# Grove_-_NFC_v1_1.net
KiCad netlist of a schematic drawn in EAGLE
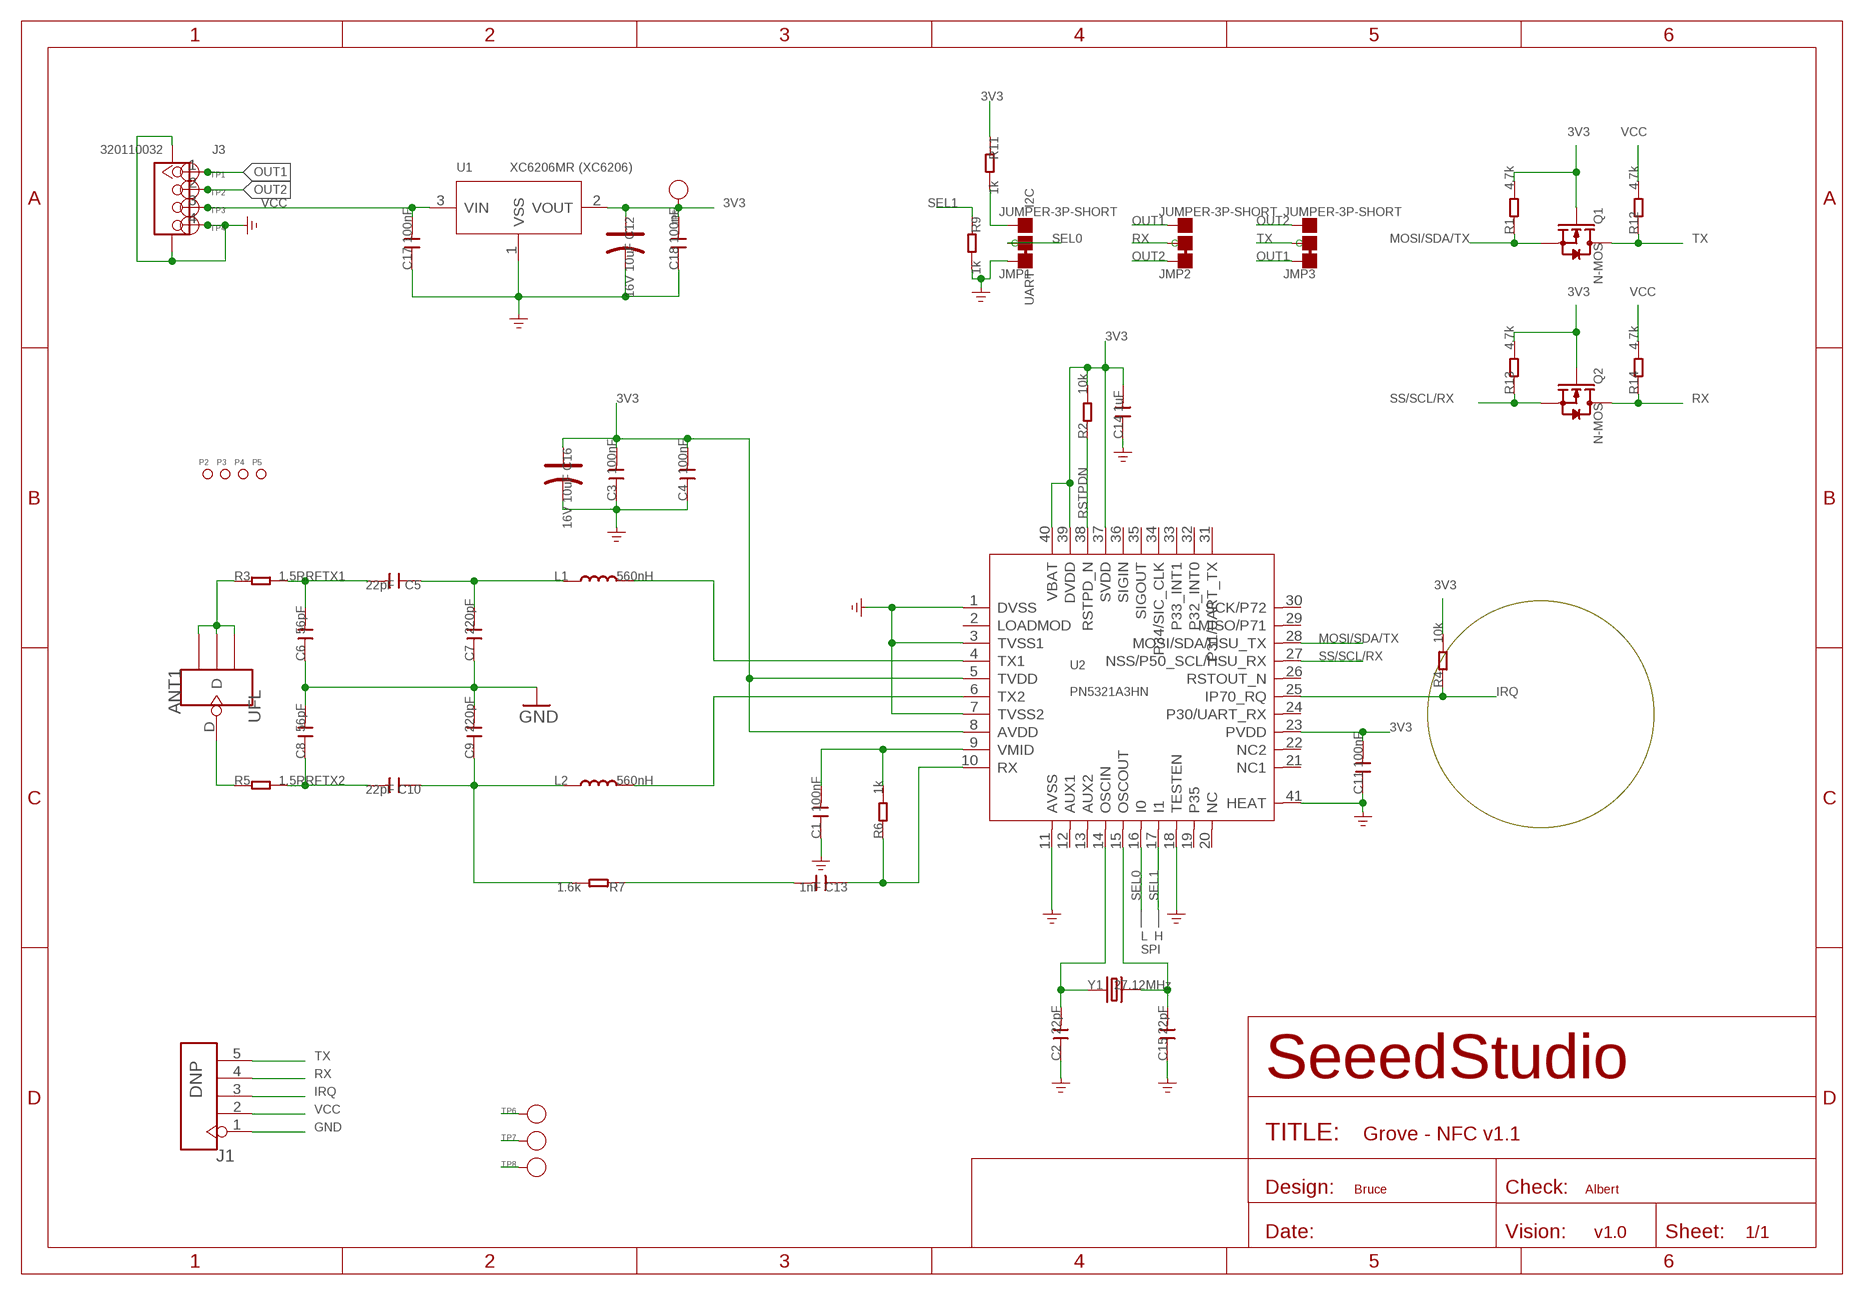
[diagram p0: schematic, sheet 1]

(export (version "E")
  (design (tool "Eeschema 10.0.6"))
  (components
    (comp (ref "ANT1")
      (value "UFL")
      (footprint "eagle-import:4P-U-FL")
      (libsource (lib "eagle-import") (part "ANTENNA-U-FL"))
    )
    (comp (ref "C1")
      (value "100nF")
      (footprint "eagle-import:C0402")
      (libsource (lib "eagle-import") (part "C-0402"))
    )
    (comp (ref "C2")
      (value "22pF")
      (footprint "eagle-import:C0402")
      (libsource (lib "eagle-import") (part "C-0402"))
    )
    (comp (ref "C3")
      (value "100nF")
      (footprint "eagle-import:C0402")
      (libsource (lib "eagle-import") (part "C-0402"))
    )
    (comp (ref "C4")
      (value "100nF")
      (footprint "eagle-import:C0402")
      (libsource (lib "eagle-import") (part "C-0402"))
    )
    (comp (ref "C5")
      (value "22pF")
      (footprint "eagle-import:C0402")
      (libsource (lib "eagle-import") (part "C-0402"))
    )
    (comp (ref "C6")
      (value "56pF")
      (footprint "eagle-import:C0402")
      (libsource (lib "eagle-import") (part "C-0402"))
    )
    (comp (ref "C7")
      (value "220pF")
      (footprint "eagle-import:C0402")
      (libsource (lib "eagle-import") (part "C-0402"))
    )
    (comp (ref "C8")
      (value "56pF")
      (footprint "eagle-import:C0402")
      (libsource (lib "eagle-import") (part "C-0402"))
    )
    (comp (ref "C9")
      (value "220pF")
      (footprint "eagle-import:C0402")
      (libsource (lib "eagle-import") (part "C-0402"))
    )
    (comp (ref "C10")
      (value "22pF")
      (footprint "eagle-import:C0402")
      (libsource (lib "eagle-import") (part "C-0402"))
    )
    (comp (ref "C11")
      (value "100nF")
      (footprint "eagle-import:C0402")
      (libsource (lib "eagle-import") (part "C-0402"))
    )
    (comp (ref "C12")
      (value "16V 10uF")
      (footprint "eagle-import:AVX-A")
      (libsource (lib "eagle-import") (part "CAP-AVX-A"))
    )
    (comp (ref "C13")
      (value "1nF")
      (footprint "eagle-import:C0402")
      (libsource (lib "eagle-import") (part "C-0402"))
    )
    (comp (ref "C14")
      (value "1uF")
      (footprint "eagle-import:C0603")
      (libsource (lib "eagle-import") (part "C-0603"))
    )
    (comp (ref "C15")
      (value "22pF")
      (footprint "eagle-import:C0402")
      (libsource (lib "eagle-import") (part "C-0402"))
    )
    (comp (ref "C16")
      (value "16V 10uF")
      (footprint "eagle-import:AVX-A")
      (libsource (lib "eagle-import") (part "CAP-AVX-A"))
    )
    (comp (ref "C17")
      (value "100nF")
      (footprint "eagle-import:C0402")
      (libsource (lib "eagle-import") (part "C-0402"))
    )
    (comp (ref "C18")
      (value "100nF")
      (footprint "eagle-import:C0402")
      (libsource (lib "eagle-import") (part "C-0402"))
    )
    (comp (ref "J1")
      (value "DNP")
      (footprint "eagle-import:5P-2.54")
      (libsource (lib "eagle-import") (part "HEADER-5P-2.54"))
    )
    (comp (ref "J3")
      (value "320110032")
      (footprint "eagle-import:4P-SMD-2.0-90D")
      (libsource (lib "eagle-import") (part "GROVE-CONNECTOR-SMD'90D'"))
    )
    (comp (ref "JMP1")
      (value "JUMPER-3P-SHORT")
      (footprint "eagle-import:3P-SMD_SHORT")
      (libsource (lib "eagle-import") (part "JUMPER-3P-SHORT"))
    )
    (comp (ref "JMP2")
      (value "JUMPER-3P-SHORT")
      (footprint "eagle-import:3P-SMD_SHORT")
      (libsource (lib "eagle-import") (part "JUMPER-3P-SHORT"))
    )
    (comp (ref "JMP3")
      (value "JUMPER-3P-SHORT")
      (footprint "eagle-import:3P-SMD_SHORT")
      (libsource (lib "eagle-import") (part "JUMPER-3P-SHORT"))
    )
    (comp (ref "L1")
      (value "560nH")
      (footprint "eagle-import:L0603")
      (libsource (lib "eagle-import") (part "L'0603'"))
    )
    (comp (ref "L2")
      (value "560nH")
      (footprint "eagle-import:L0603")
      (libsource (lib "eagle-import") (part "L'0603'"))
    )
    (comp (ref "P2")
      (value "DNP")
      (footprint "eagle-import:ROUND-MARK-1.0")
      (libsource (lib "eagle-import") (part "PAD-MARK"))
    )
    (comp (ref "P3")
      (value "DNP")
      (footprint "eagle-import:ROUND-MARK-1.0")
      (libsource (lib "eagle-import") (part "PAD-MARK"))
    )
    (comp (ref "P4")
      (value "DNP")
      (footprint "eagle-import:ROUND-MARK-1.0")
      (libsource (lib "eagle-import") (part "PAD-MARK"))
    )
    (comp (ref "P5")
      (value "DNP")
      (footprint "eagle-import:ROUND-MARK-1.0")
      (libsource (lib "eagle-import") (part "PAD-MARK"))
    )
    (comp (ref "Q1")
      (value "N-MOS")
      (footprint "eagle-import:SOT23")
      (libsource (lib "eagle-import") (part "MOSFET-N'SOT23'"))
    )
    (comp (ref "Q2")
      (value "N-MOS")
      (footprint "eagle-import:SOT23")
      (libsource (lib "eagle-import") (part "MOSFET-N'SOT23'"))
    )
    (comp (ref "R1")
      (value "4.7k")
      (footprint "eagle-import:R0402")
      (libsource (lib "eagle-import") (part "R-0402"))
    )
    (comp (ref "R2")
      (value "10k")
      (footprint "eagle-import:R0402")
      (libsource (lib "eagle-import") (part "R-0402"))
    )
    (comp (ref "R3")
      (value "1.5R")
      (footprint "eagle-import:R0402")
      (libsource (lib "eagle-import") (part "R-0402"))
    )
    (comp (ref "R4")
      (value "10k")
      (footprint "eagle-import:R0402")
      (libsource (lib "eagle-import") (part "R-0402"))
    )
    (comp (ref "R5")
      (value "1.5R")
      (footprint "eagle-import:R0402")
      (libsource (lib "eagle-import") (part "R-0402"))
    )
    (comp (ref "R6")
      (value "1k")
      (footprint "eagle-import:R0402")
      (libsource (lib "eagle-import") (part "R-0402"))
    )
    (comp (ref "R7")
      (value "1.6k")
      (footprint "eagle-import:R0402")
      (libsource (lib "eagle-import") (part "R-0402"))
    )
    (comp (ref "R9")
      (value "1k")
      (footprint "eagle-import:R0402")
      (libsource (lib "eagle-import") (part "R-0402"))
    )
    (comp (ref "R11")
      (value "1k")
      (footprint "eagle-import:R0402")
      (libsource (lib "eagle-import") (part "R-0402"))
    )
    (comp (ref "R12")
      (value "4.7k")
      (footprint "eagle-import:R0402")
      (libsource (lib "eagle-import") (part "R-0402"))
    )
    (comp (ref "R13")
      (value "4.7k")
      (footprint "eagle-import:R0402")
      (libsource (lib "eagle-import") (part "R-0402"))
    )
    (comp (ref "R14")
      (value "4.7k")
      (footprint "eagle-import:R0402")
      (libsource (lib "eagle-import") (part "R-0402"))
    )
    (comp (ref "TP1")
      (value "DNP")
      (footprint "eagle-import:TP_4545")
      (libsource (lib "eagle-import") (part "PAD-TEST-POINT'4545'"))
    )
    (comp (ref "TP2")
      (value "DNP")
      (footprint "eagle-import:TP_4545")
      (libsource (lib "eagle-import") (part "PAD-TEST-POINT'4545'"))
    )
    (comp (ref "TP3")
      (value "DNP")
      (footprint "eagle-import:TP_4545")
      (libsource (lib "eagle-import") (part "PAD-TEST-POINT'4545'"))
    )
    (comp (ref "TP4")
      (value "DNP")
      (footprint "eagle-import:TP_4545")
      (libsource (lib "eagle-import") (part "PAD-TEST-POINT'4545'"))
    )
    (comp (ref "TP5")
      (value "DNP")
      (footprint "eagle-import:TP_4545")
      (libsource (lib "eagle-import") (part "PAD-TEST-POINT'4545'"))
    )
    (comp (ref "TP6")
      (value "DNP")
      (footprint "eagle-import:TP_4545")
      (libsource (lib "eagle-import") (part "PAD-TEST-POINT'4545'"))
    )
    (comp (ref "TP7")
      (value "DNP")
      (footprint "eagle-import:TP_4545")
      (libsource (lib "eagle-import") (part "PAD-TEST-POINT'4545'"))
    )
    (comp (ref "TP8")
      (value "DNP")
      (footprint "eagle-import:TP_4545")
      (libsource (lib "eagle-import") (part "PAD-TEST-POINT'4545'"))
    )
    (comp (ref "U1")
      (value "XC6206MR (XC6206)")
      (footprint "eagle-import:SOT-23")
      (libsource (lib "eagle-import") (part "PMIC-XC6206PMR"))
    )
    (comp (ref "U2")
      (value "PN5321A3HN")
      (footprint "eagle-import:HVQFN40")
      (libsource (lib "eagle-import") (part "PN532-HVQFN40"))
    )
    (comp (ref "Y1")
      (value "27.12MHz")
      (footprint "eagle-import:4P-SMD-3.2X2.5")
      (libsource (lib "eagle-import") (part "CRYSTAL'3225'"))
    )
  )
  (nets
    (net (code "1") (name "/3V3") (class "Default")
      (node (ref "C11") (pin "2") (pinfunction "2_2") (pintype "passive"))
      (node (ref "C12") (pin "+") (pinfunction "+_+") (pintype "passive"))
      (node (ref "C14") (pin "2") (pinfunction "2_2") (pintype "passive"))
      (node (ref "C16") (pin "+") (pinfunction "+_+") (pintype "passive"))
      (node (ref "C18") (pin "2") (pinfunction "2_2") (pintype "passive"))
      (node (ref "C3") (pin "2") (pinfunction "2_2") (pintype "passive"))
      (node (ref "C4") (pin "2") (pinfunction "2_2") (pintype "passive"))
      (node (ref "Q1") (pin "1") (pinfunction "G_1") (pintype "passive"))
      (node (ref "Q2") (pin "1") (pinfunction "G_1") (pintype "passive"))
      (node (ref "R1") (pin "2") (pinfunction "2_2") (pintype "passive"))
      (node (ref "R11") (pin "1") (pinfunction "1_1") (pintype "passive"))
      (node (ref "R13") (pin "2") (pinfunction "2_2") (pintype "passive"))
      (node (ref "R2") (pin "2") (pinfunction "2_2") (pintype "passive"))
      (node (ref "R4") (pin "2") (pinfunction "2_2") (pintype "passive"))
      (node (ref "TP5") (pin "T") (pinfunction "T_T") (pintype "bidirectional"))
      (node (ref "U1") (pin "2") (pinfunction "VOUT_2") (pintype "output"))
      (node (ref "U2") (pin "23") (pinfunction "PVDD_23") (pintype "power_in"))
      (node (ref "U2") (pin "37") (pinfunction "SVDD_37") (pintype "power_in"))
      (node (ref "U2") (pin "39") (pinfunction "DVDD_39") (pintype "power_in"))
      (node (ref "U2") (pin "40") (pinfunction "VBAT_40") (pintype "power_in"))
      (node (ref "U2") (pin "5") (pinfunction "TVDD_5") (pintype "power_in"))
      (node (ref "U2") (pin "8") (pinfunction "AVDD_8") (pintype "power_in"))
    )
    (net (code "2") (name "/IRQ") (class "Default")
      (node (ref "J1") (pin "3") (pinfunction "3_3") (pintype "bidirectional"))
      (node (ref "R4") (pin "1") (pinfunction "1_1") (pintype "passive"))
      (node (ref "U2") (pin "25") (pinfunction "IP70_RQ_25") (pintype "output"))
    )
    (net (code "3") (name "/MOSI{slash}SDA{slash}TX") (class "Default")
      (node (ref "Q1") (pin "2") (pinfunction "S_2") (pintype "passive"))
      (node (ref "R1") (pin "1") (pinfunction "1_1") (pintype "passive"))
      (node (ref "U2") (pin "28") (pinfunction "MOSI/SDA/HSU_TX_28") (pintype "bidirectional"))
    )
    (net (code "4") (name "/RFTX1") (class "Default")
      (node (ref "C5") (pin "2") (pinfunction "2_2") (pintype "passive"))
      (node (ref "C6") (pin "2") (pinfunction "2_2") (pintype "passive"))
      (node (ref "R3") (pin "2") (pinfunction "2_2") (pintype "passive"))
    )
    (net (code "5") (name "/RFTX2") (class "Default")
      (node (ref "C10") (pin "2") (pinfunction "2_2") (pintype "passive"))
      (node (ref "C8") (pin "1") (pinfunction "1_1") (pintype "passive"))
      (node (ref "R5") (pin "2") (pinfunction "2_2") (pintype "passive"))
    )
    (net (code "6") (name "/RSTPDN") (class "Default")
      (node (ref "R2") (pin "1") (pinfunction "1_1") (pintype "passive"))
      (node (ref "U2") (pin "38") (pinfunction "RSTPD_N_38") (pintype "input"))
    )
    (net (code "7") (name "/RX") (class "Default")
      (node (ref "J1") (pin "4") (pinfunction "4_4") (pintype "bidirectional"))
      (node (ref "JMP2") (pin "MM") (pinfunction "C_MM") (pintype "bidirectional"))
      (node (ref "Q2") (pin "3") (pinfunction "D_3") (pintype "passive"))
      (node (ref "R14") (pin "1") (pinfunction "1_1") (pintype "passive"))
    )
    (net (code "8") (name "/SEL0") (class "Default")
      (node (ref "JMP1") (pin "MM") (pinfunction "C_MM") (pintype "bidirectional"))
      (node (ref "U2") (pin "16") (pinfunction "I0_16") (pintype "input"))
    )
    (net (code "9") (name "/SEL1") (class "Default")
      (node (ref "R9") (pin "1") (pinfunction "1_1") (pintype "passive"))
      (node (ref "U2") (pin "17") (pinfunction "I1_17") (pintype "input"))
    )
    (net (code "10") (name "/SS{slash}SCL{slash}RX") (class "Default")
      (node (ref "Q2") (pin "2") (pinfunction "S_2") (pintype "passive"))
      (node (ref "R13") (pin "1") (pinfunction "1_1") (pintype "passive"))
      (node (ref "U2") (pin "27") (pinfunction "NSS/P50_SCL/HSU_RX_27") (pintype "bidirectional"))
    )
    (net (code "11") (name "/TX") (class "Default")
      (node (ref "J1") (pin "5") (pinfunction "5_5") (pintype "bidirectional"))
      (node (ref "JMP3") (pin "MM") (pinfunction "C_MM") (pintype "bidirectional"))
      (node (ref "Q1") (pin "3") (pinfunction "D_3") (pintype "passive"))
      (node (ref "R12") (pin "1") (pinfunction "1_1") (pintype "passive"))
    )
    (net (code "12") (name "/VCC") (class "Default")
      (node (ref "C17") (pin "2") (pinfunction "2_2") (pintype "passive"))
      (node (ref "J1") (pin "2") (pinfunction "2_2") (pintype "bidirectional"))
      (node (ref "J3") (pin "3") (pinfunction "3_3") (pintype "bidirectional"))
      (node (ref "R12") (pin "2") (pinfunction "2_2") (pintype "passive"))
      (node (ref "R14") (pin "2") (pinfunction "2_2") (pintype "passive"))
      (node (ref "TP3") (pin "T") (pinfunction "T_T") (pintype "bidirectional"))
      (node (ref "U1") (pin "3") (pinfunction "VIN_3") (pintype "input"))
    )
    (net (code "13") (name "GND") (class "Default")
      (node (ref "C1") (pin "1") (pinfunction "1_1") (pintype "passive"))
      (node (ref "C11") (pin "1") (pinfunction "1_1") (pintype "passive"))
      (node (ref "C12") (pin "-") (pinfunction "-_-") (pintype "passive"))
      (node (ref "C14") (pin "1") (pinfunction "1_1") (pintype "passive"))
      (node (ref "C15") (pin "1") (pinfunction "1_1") (pintype "passive"))
      (node (ref "C16") (pin "-") (pinfunction "-_-") (pintype "passive"))
      (node (ref "C17") (pin "1") (pinfunction "1_1") (pintype "passive"))
      (node (ref "C18") (pin "1") (pinfunction "1_1") (pintype "passive"))
      (node (ref "C2") (pin "1") (pinfunction "1_1") (pintype "passive"))
      (node (ref "C3") (pin "1") (pinfunction "1_1") (pintype "passive"))
      (node (ref "C4") (pin "1") (pinfunction "1_1") (pintype "passive"))
      (node (ref "C6") (pin "1") (pinfunction "1_1") (pintype "passive"))
      (node (ref "C7") (pin "1") (pinfunction "1_1") (pintype "passive"))
      (node (ref "C8") (pin "2") (pinfunction "2_2") (pintype "passive"))
      (node (ref "C9") (pin "2") (pinfunction "2_2") (pintype "passive"))
      (node (ref "J1") (pin "1") (pinfunction "1_1") (pintype "bidirectional"))
      (node (ref "J3") (pin "4") (pinfunction "4_4") (pintype "bidirectional"))
      (node (ref "J3") (pin "SS1") (pinfunction "SS1_SS1") (pintype "bidirectional"))
      (node (ref "J3") (pin "SS2") (pinfunction "SS2_SS2") (pintype "bidirectional"))
      (node (ref "JMP1") (pin "11") (pinfunction "L_11") (pintype "bidirectional"))
      (node (ref "R9") (pin "2") (pinfunction "2_2") (pintype "passive"))
      (node (ref "TP4") (pin "T") (pinfunction "T_T") (pintype "bidirectional"))
      (node (ref "U1") (pin "1") (pinfunction "VSS_1") (pintype "power_in"))
      (node (ref "U2") (pin "1") (pinfunction "DVSS_1") (pintype "power_in"))
      (node (ref "U2") (pin "11") (pinfunction "AVSS_11") (pintype "power_in"))
      (node (ref "U2") (pin "18") (pinfunction "TESTEN_18") (pintype "input"))
      (node (ref "U2") (pin "3") (pinfunction "TVSS1_3") (pintype "power_in"))
      (node (ref "U2") (pin "41") (pinfunction "HEAT_41") (pintype "bidirectional"))
      (node (ref "U2") (pin "7") (pinfunction "TVSS2_7") (pintype "power_in"))
    )
    (net (code "14") (name "Net-(ANT1-PadD)") (class "Default")
      (node (ref "ANT1") (pin "D") (pinfunction "D_D") (pintype "bidirectional"))
      (node (ref "R5") (pin "1") (pinfunction "1_1") (pintype "passive"))
    )
    (net (code "15") (name "Net-(ANT1-PadGND1)") (class "Default")
      (node (ref "ANT1") (pin "GND1") (pinfunction "GND1_GND1") (pintype "bidirectional"))
      (node (ref "ANT1") (pin "GND2") (pinfunction "GND2_GND2") (pintype "bidirectional"))
      (node (ref "ANT1") (pin "GND3") (pinfunction "GND3_GND3") (pintype "bidirectional"))
      (node (ref "R3") (pin "1") (pinfunction "1_1") (pintype "passive"))
    )
    (net (code "16") (name "Net-(C5-Pad1)") (class "Default")
      (node (ref "C5") (pin "1") (pinfunction "1_1") (pintype "passive"))
      (node (ref "C7") (pin "2") (pinfunction "2_2") (pintype "passive"))
      (node (ref "L1") (pin "1") (pinfunction "1_1") (pintype "passive"))
    )
    (net (code "17") (name "Net-(C10-Pad1)") (class "Default")
      (node (ref "C10") (pin "1") (pinfunction "1_1") (pintype "passive"))
      (node (ref "C9") (pin "1") (pinfunction "1_1") (pintype "passive"))
      (node (ref "L2") (pin "1") (pinfunction "1_1") (pintype "passive"))
      (node (ref "R7") (pin "2") (pinfunction "2_2") (pintype "passive"))
    )
    (net (code "18") (name "Net-(C13-Pad2)") (class "Default")
      (node (ref "C13") (pin "2") (pinfunction "2_2") (pintype "passive"))
      (node (ref "R7") (pin "1") (pinfunction "1_1") (pintype "passive"))
    )
    (net (code "19") (name "Net-(JMP1-R)") (class "Default")
      (node (ref "JMP1") (pin "00") (pinfunction "R_00") (pintype "bidirectional"))
      (node (ref "R11") (pin "2") (pinfunction "2_2") (pintype "passive"))
    )
    (net (code "20") (name "Net-(U2-OSCIN)") (class "Default")
      (node (ref "C2") (pin "2") (pinfunction "2_2") (pintype "passive"))
      (node (ref "U2") (pin "14") (pinfunction "OSCIN_14") (pintype "input"))
      (node (ref "Y1") (pin "2") (pinfunction "1_2") (pintype "passive"))
    )
    (net (code "21") (name "Net-(U2-OSCOUT)") (class "Default")
      (node (ref "C15") (pin "2") (pinfunction "2_2") (pintype "passive"))
      (node (ref "U2") (pin "15") (pinfunction "OSCOUT_15") (pintype "output"))
      (node (ref "Y1") (pin "4") (pinfunction "2_4") (pintype "passive"))
    )
    (net (code "22") (name "Net-(U2-RX)") (class "Default")
      (node (ref "C13") (pin "1") (pinfunction "1_1") (pintype "passive"))
      (node (ref "R6") (pin "1") (pinfunction "1_1") (pintype "passive"))
      (node (ref "U2") (pin "10") (pinfunction "RX_10") (pintype "input"))
    )
    (net (code "23") (name "Net-(U2-TX1)") (class "Default")
      (node (ref "L1") (pin "2") (pinfunction "2_2") (pintype "passive"))
      (node (ref "U2") (pin "4") (pinfunction "TX1_4") (pintype "output"))
    )
    (net (code "24") (name "Net-(U2-TX2)") (class "Default")
      (node (ref "L2") (pin "2") (pinfunction "2_2") (pintype "passive"))
      (node (ref "U2") (pin "6") (pinfunction "TX2_6") (pintype "output"))
    )
    (net (code "25") (name "Net-(U2-VMID)") (class "Default")
      (node (ref "C1") (pin "2") (pinfunction "2_2") (pintype "passive"))
      (node (ref "R6") (pin "2") (pinfunction "2_2") (pintype "passive"))
      (node (ref "U2") (pin "9") (pinfunction "VMID_9") (pintype "output"))
    )
    (net (code "26") (name "OUT1") (class "Default")
      (node (ref "J3") (pin "1") (pinfunction "1_1") (pintype "bidirectional"))
      (node (ref "JMP2") (pin "00") (pinfunction "R_00") (pintype "bidirectional"))
      (node (ref "JMP3") (pin "11") (pinfunction "L_11") (pintype "bidirectional"))
      (node (ref "TP1") (pin "T") (pinfunction "T_T") (pintype "bidirectional"))
    )
    (net (code "27") (name "OUT2") (class "Default")
      (node (ref "J3") (pin "2") (pinfunction "2_2") (pintype "bidirectional"))
      (node (ref "JMP2") (pin "11") (pinfunction "L_11") (pintype "bidirectional"))
      (node (ref "JMP3") (pin "00") (pinfunction "R_00") (pintype "bidirectional"))
      (node (ref "TP2") (pin "T") (pinfunction "T_T") (pintype "bidirectional"))
    )
    (net (code "28") (name "unconnected-(TP6-PadT)") (class "Default")
      (node (ref "TP6") (pin "T") (pinfunction "T_T") (pintype "bidirectional"))
    )
    (net (code "29") (name "unconnected-(TP7-PadT)") (class "Default")
      (node (ref "TP7") (pin "T") (pinfunction "T_T") (pintype "bidirectional"))
    )
    (net (code "30") (name "unconnected-(TP8-PadT)") (class "Default")
      (node (ref "TP8") (pin "T") (pinfunction "T_T") (pintype "bidirectional"))
    )
    (net (code "31") (name "unconnected-(U2-AUX1-Pad12)") (class "Default")
      (node (ref "U2") (pin "12") (pinfunction "AUX1_12") (pintype "output"))
    )
    (net (code "32") (name "unconnected-(U2-AUX2-Pad13)") (class "Default")
      (node (ref "U2") (pin "13") (pinfunction "AUX2_13") (pintype "output"))
    )
    (net (code "33") (name "unconnected-(U2-LOADMOD-Pad2)") (class "Default")
      (node (ref "U2") (pin "2") (pinfunction "LOADMOD_2") (pintype "output"))
    )
    (net (code "34") (name "unconnected-(U2-MISO{slash}P71-Pad29)") (class "Default")
      (node (ref "U2") (pin "29") (pinfunction "MISO/P71_29") (pintype "bidirectional"))
    )
    (net (code "35") (name "unconnected-(U2-NC-Pad20)") (class "Default")
      (node (ref "U2") (pin "20") (pinfunction "NC_20") (pintype "no_connect"))
    )
    (net (code "36") (name "unconnected-(U2-NC1-Pad21)") (class "Default")
      (node (ref "U2") (pin "21") (pinfunction "NC1_21") (pintype "no_connect"))
    )
    (net (code "37") (name "unconnected-(U2-NC2-Pad22)") (class "Default")
      (node (ref "U2") (pin "22") (pinfunction "NC2_22") (pintype "no_connect"))
    )
    (net (code "38") (name "unconnected-(U2-P30{slash}UART_RX-Pad24)") (class "Default")
      (node (ref "U2") (pin "24") (pinfunction "P30/UART_RX_24") (pintype "bidirectional"))
    )
    (net (code "39") (name "unconnected-(U2-P31{slash}UART_TX-Pad31)") (class "Default")
      (node (ref "U2") (pin "31") (pinfunction "P31/UART_TX_31") (pintype "bidirectional"))
    )
    (net (code "40") (name "unconnected-(U2-P32_INT0-Pad32)") (class "Default")
      (node (ref "U2") (pin "32") (pinfunction "P32_INT0_32") (pintype "bidirectional"))
    )
    (net (code "41") (name "unconnected-(U2-P33_INT1-Pad33)") (class "Default")
      (node (ref "U2") (pin "33") (pinfunction "P33_INT1_33") (pintype "bidirectional"))
    )
    (net (code "42") (name "unconnected-(U2-P34{slash}SIC_CLK-Pad34)") (class "Default")
      (node (ref "U2") (pin "34") (pinfunction "P34/SIC_CLK_34") (pintype "bidirectional"))
    )
    (net (code "43") (name "unconnected-(U2-P35-Pad19)") (class "Default")
      (node (ref "U2") (pin "19") (pinfunction "P35_19") (pintype "bidirectional"))
    )
    (net (code "44") (name "unconnected-(U2-RSTOUT_N-Pad26)") (class "Default")
      (node (ref "U2") (pin "26") (pinfunction "RSTOUT_N_26") (pintype "bidirectional"))
    )
    (net (code "45") (name "unconnected-(U2-SCK{slash}P72-Pad30)") (class "Default")
      (node (ref "U2") (pin "30") (pinfunction "SCK/P72_30") (pintype "bidirectional"))
    )
    (net (code "46") (name "unconnected-(U2-SIGIN-Pad36)") (class "Default")
      (node (ref "U2") (pin "36") (pinfunction "SIGIN_36") (pintype "input"))
    )
    (net (code "47") (name "unconnected-(U2-SIGOUT-Pad35)") (class "Default")
      (node (ref "U2") (pin "35") (pinfunction "SIGOUT_35") (pintype "output"))
    )
  )
)
